# DRV8701E_jzk.net
KiCad netlist of a schematic drawn in EasyEDA Pro
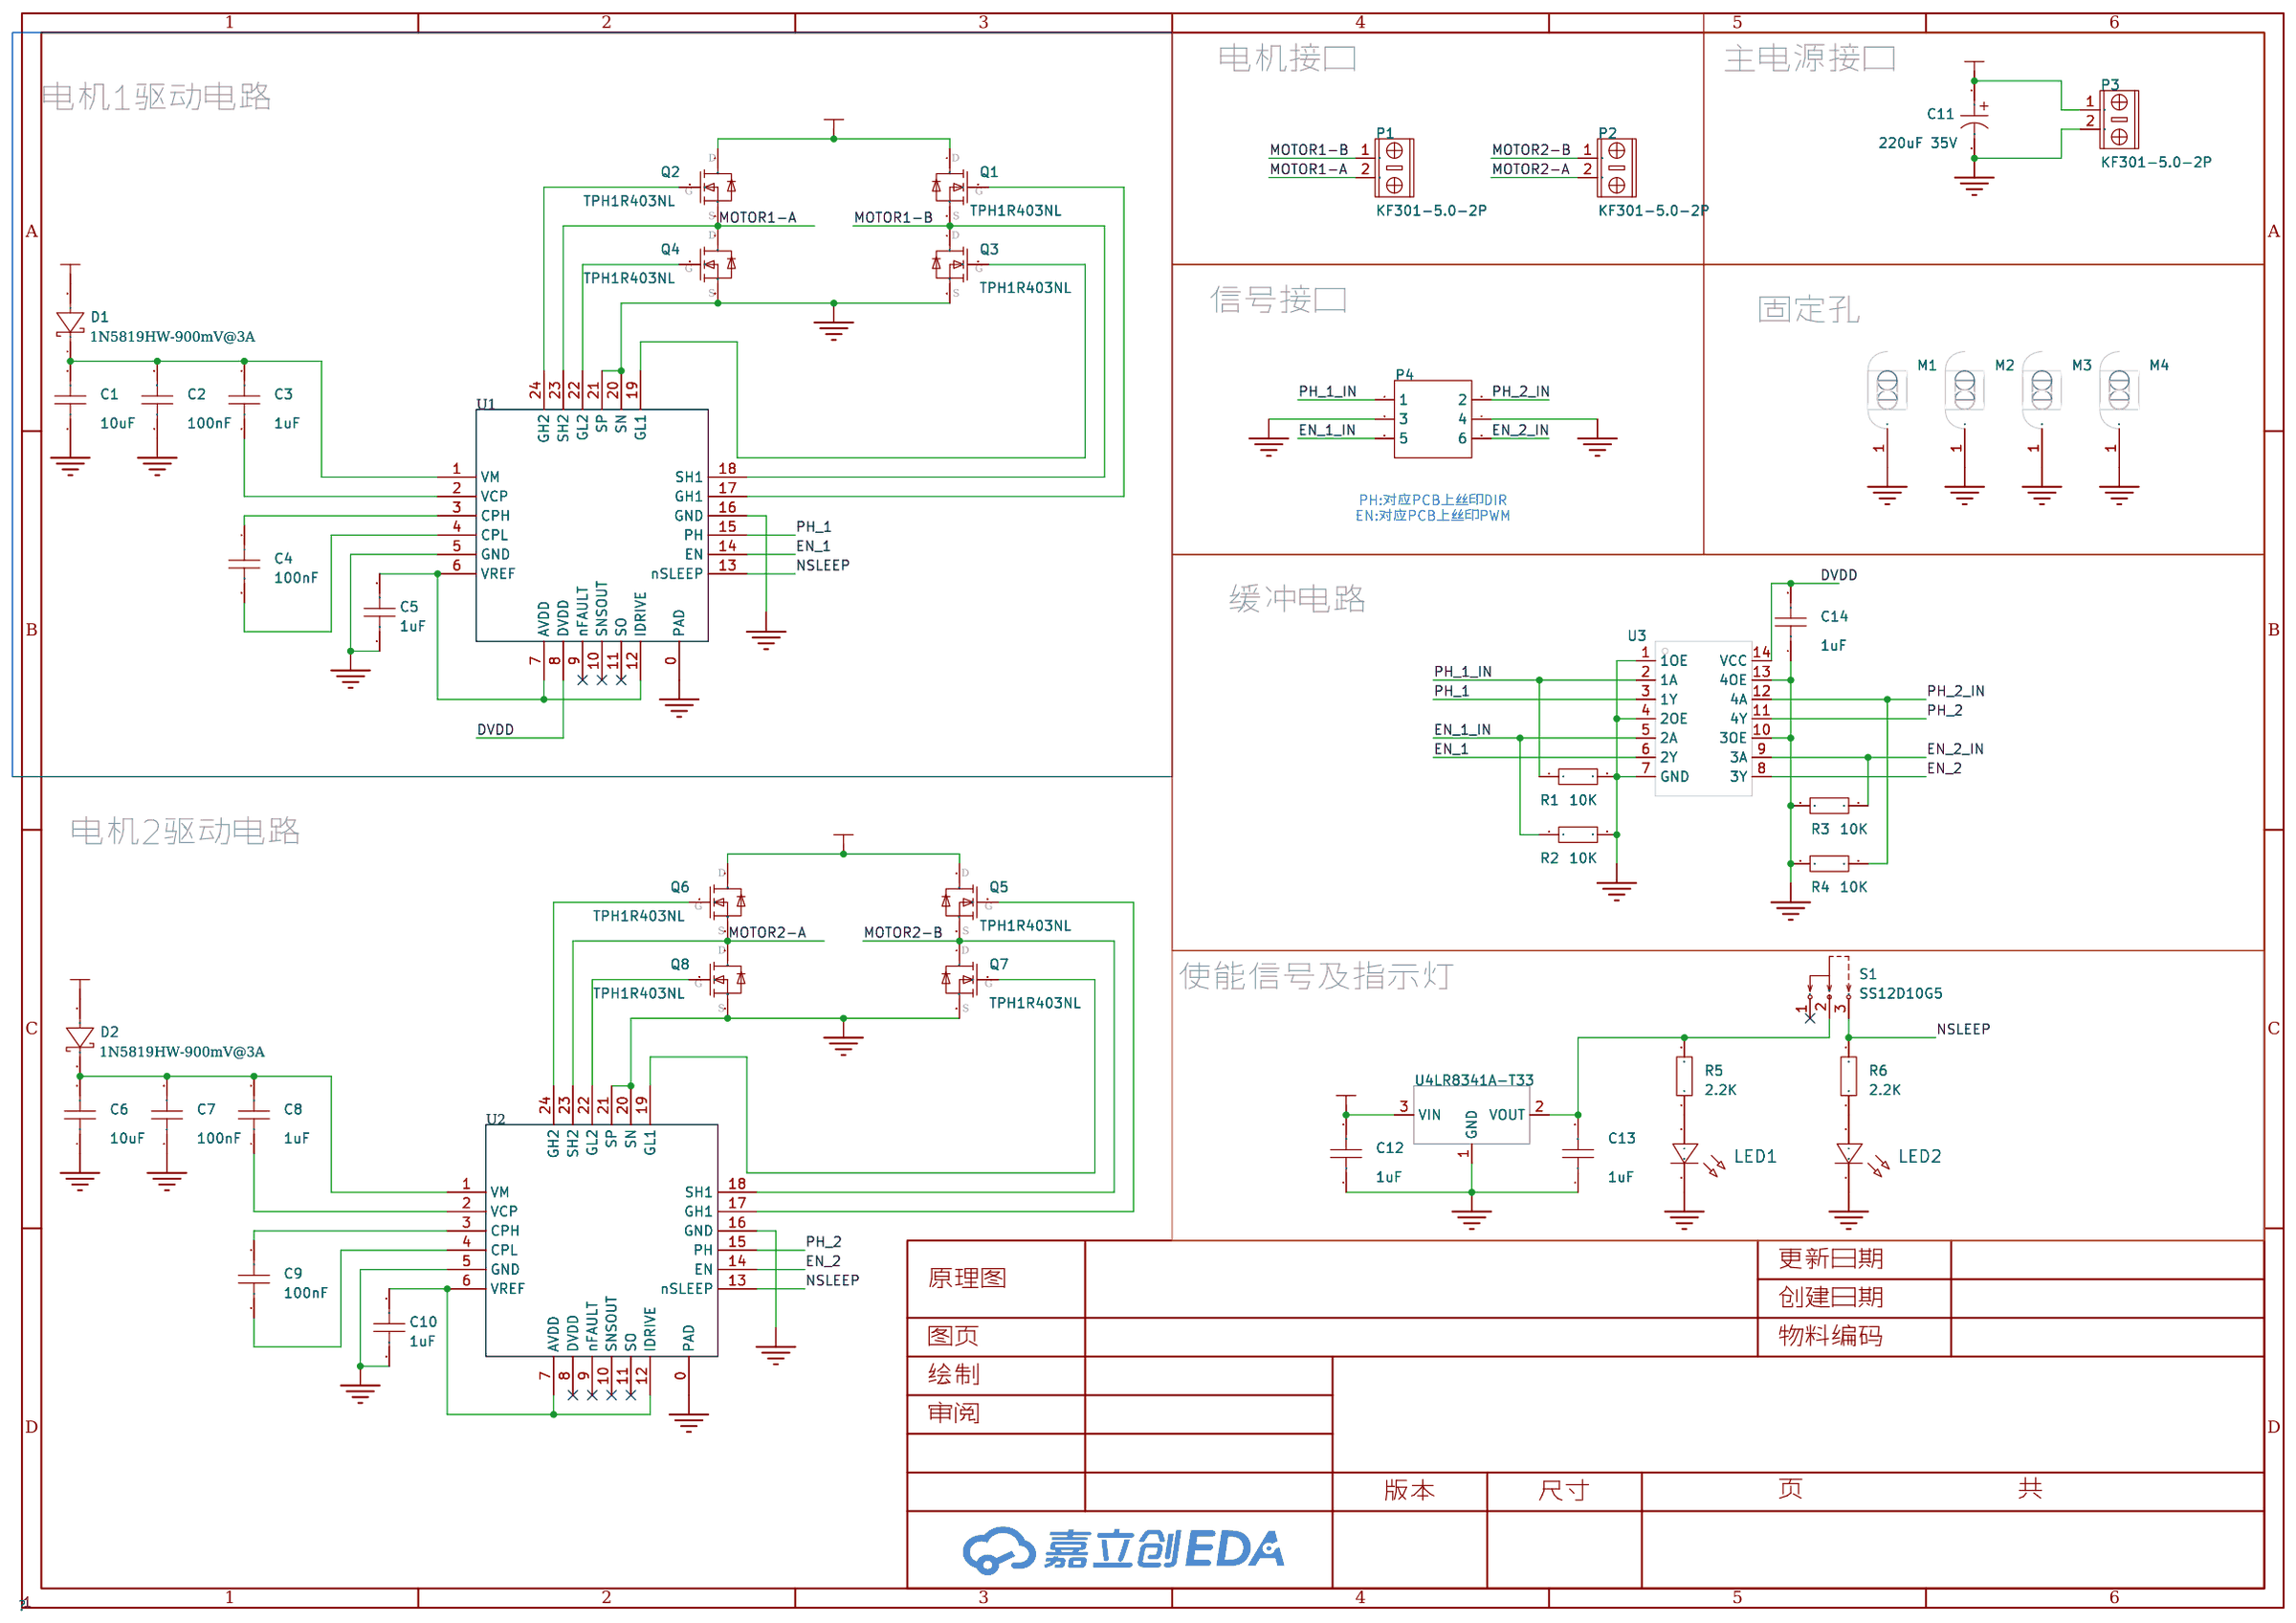
[diagram p0: schematic sheet]

(export (version "E")
  (design (tool "Eeschema 10.0.6"))
  (components
    (comp (ref "C1")
      (value "10uF")
      (footprint "easyedapro:C0805")
      (libsource (lib "easyedapro") (part "CapAcitance"))
    )
    (comp (ref "C2")
      (value "100nF")
      (footprint "easyedapro:C0805")
      (libsource (lib "easyedapro") (part "CapAcitance"))
    )
    (comp (ref "C3")
      (value "1uF")
      (footprint "easyedapro:C0805")
      (libsource (lib "easyedapro") (part "CapAcitance"))
    )
    (comp (ref "C4")
      (value "100nF")
      (footprint "easyedapro:C0805")
      (libsource (lib "easyedapro") (part "CapAcitance"))
    )
    (comp (ref "C5")
      (value "1uF")
      (footprint "easyedapro:C0805")
      (libsource (lib "easyedapro") (part "CapAcitance"))
    )
    (comp (ref "C6")
      (value "10uF")
      (footprint "easyedapro:C0805")
      (libsource (lib "easyedapro") (part "CapAcitance"))
    )
    (comp (ref "C7")
      (value "100nF")
      (footprint "easyedapro:C0805")
      (libsource (lib "easyedapro") (part "CapAcitance"))
    )
    (comp (ref "C8")
      (value "1uF")
      (footprint "easyedapro:C0805")
      (libsource (lib "easyedapro") (part "CapAcitance"))
    )
    (comp (ref "C9")
      (value "100nF")
      (footprint "easyedapro:C0805")
      (libsource (lib "easyedapro") (part "CapAcitance"))
    )
    (comp (ref "C10")
      (value "1uF")
      (footprint "easyedapro:C0805")
      (libsource (lib "easyedapro") (part "CapAcitance"))
    )
    (comp (ref "C11")
      (value "220uF 35V")
      (footprint "easyedapro:CAP-TH_BD8.0-P3.50-D0.6-FD-2")
      (description "容值:220uF;精度:±20%;额定电压:35V;纹波电流:1.7A@100kHz;等效串联电阻:40mΩ@100kHz;")
      (fields
        (field (name "Manufacturer Part") "KNH2220UF35V149EC0049")
        (field (name "Manufacturer") "KNSCHA(科尼盛)")
      )
      (libsource (lib "easyedapro") (part "KNH2220UF35V149EC0049"))
    )
    (comp (ref "C12")
      (value "1uF")
      (footprint "easyedapro:C0805")
      (libsource (lib "easyedapro") (part "CapAcitance"))
    )
    (comp (ref "C13")
      (value "1uF")
      (footprint "easyedapro:C0805")
      (libsource (lib "easyedapro") (part "CapAcitance"))
    )
    (comp (ref "C14")
      (value "1uF")
      (footprint "easyedapro:C0805")
      (libsource (lib "easyedapro") (part "CapAcitance"))
    )
    (comp (ref "D1")
      (value "1N5819HW-900mV@3A")
      (footprint "easyedapro:SOD-123_L2.7-W1.6-LS3.7-RD-1")
      (description "二极管配置:-;正向压降(Vf):900mV@3A;直流反向耐压(Vr):40V;平均整流电流(Io):1A;")
      (fields (field (name "Manufacturer") "TECH PUBLIC(台舟)"))
      (libsource (lib "easyedapro") (part "1N5819W_C2905650"))
    )
    (comp (ref "D2")
      (value "1N5819HW-900mV@3A")
      (footprint "easyedapro:SOD-123_L2.7-W1.6-LS3.7-RD-1")
      (description "二极管配置:-;正向压降(Vf):900mV@3A;直流反向耐压(Vr):40V;平均整流电流(Io):1A;")
      (fields (field (name "Manufacturer") "TECH PUBLIC(台舟)"))
      (libsource (lib "easyedapro") (part "1N5819W_C2905650"))
    )
    (comp (ref "LED1")
      (value "~")
      (footprint "easyedapro:LED_0603")
      (libsource (lib "easyedapro") (part "LED_R"))
    )
    (comp (ref "LED2")
      (value "~")
      (footprint "easyedapro:LED_0603")
      (libsource (lib "easyedapro") (part "LED_R"))
    )
    (comp (ref "M1")
      (value "~")
      (footprint "easyedapro:长圆形固定孔L5.0-O3.0")
      (libsource (lib "easyedapro") (part "长圆形固定孔L5.0-O3.0"))
    )
    (comp (ref "M2")
      (value "~")
      (footprint "easyedapro:长圆形固定孔L5.0-O3.0")
      (libsource (lib "easyedapro") (part "长圆形固定孔L5.0-O3.0"))
    )
    (comp (ref "M3")
      (value "~")
      (footprint "easyedapro:长圆形固定孔L5.0-O3.0")
      (libsource (lib "easyedapro") (part "长圆形固定孔L5.0-O3.0"))
    )
    (comp (ref "M4")
      (value "~")
      (footprint "easyedapro:长圆形固定孔L5.0-O3.0")
      (libsource (lib "easyedapro") (part "长圆形固定孔L5.0-O3.0"))
    )
    (comp (ref "P1")
      (value "KF301-5.0-2P")
      (footprint "easyedapro:CONN-TH_P5.00_KF301-5.0-2P")
      (fields (field (name "Manufacturer") "KEFA(科发)"))
      (libsource (lib "easyedapro") (part "KF301-5.0-2P"))
    )
    (comp (ref "P2")
      (value "KF301-5.0-2P")
      (footprint "easyedapro:CONN-TH_P5.00_KF301-5.0-2P")
      (fields (field (name "Manufacturer") "KEFA(科发)"))
      (libsource (lib "easyedapro") (part "KF301-5.0-2P"))
    )
    (comp (ref "P3")
      (value "KF301-5.0-2P")
      (footprint "easyedapro:CONN-TH_P5.00_KF301-5.0-2P")
      (fields (field (name "Manufacturer") "KEFA(科发)"))
      (libsource (lib "easyedapro") (part "KF301-5.0-2P"))
    )
    (comp (ref "P4")
      (value "~")
      (footprint "easyedapro:HDR-TH_6P-P2.54-V-F-R2-C3-S2.54")
      (libsource (lib "easyedapro") (part "HDR-F-2.54_2x3"))
    )
    (comp (ref "Q1")
      (value "TPH1R403NL")
      (footprint "easyedapro:DFN5x6")
      (libsource (lib "easyedapro") (part "TPH1R403NL"))
    )
    (comp (ref "Q2")
      (value "TPH1R403NL")
      (footprint "easyedapro:DFN5x6")
      (libsource (lib "easyedapro") (part "TPH1R403NL"))
    )
    (comp (ref "Q3")
      (value "TPH1R403NL")
      (footprint "easyedapro:DFN5x6")
      (libsource (lib "easyedapro") (part "TPH1R403NL"))
    )
    (comp (ref "Q4")
      (value "TPH1R403NL")
      (footprint "easyedapro:DFN5x6")
      (libsource (lib "easyedapro") (part "TPH1R403NL"))
    )
    (comp (ref "Q5")
      (value "TPH1R403NL")
      (footprint "easyedapro:DFN5x6")
      (libsource (lib "easyedapro") (part "TPH1R403NL"))
    )
    (comp (ref "Q6")
      (value "TPH1R403NL")
      (footprint "easyedapro:DFN5x6")
      (libsource (lib "easyedapro") (part "TPH1R403NL"))
    )
    (comp (ref "Q7")
      (value "TPH1R403NL")
      (footprint "easyedapro:DFN5x6")
      (libsource (lib "easyedapro") (part "TPH1R403NL"))
    )
    (comp (ref "Q8")
      (value "TPH1R403NL")
      (footprint "easyedapro:DFN5x6")
      (libsource (lib "easyedapro") (part "TPH1R403NL"))
    )
    (comp (ref "R1") (value "10K") (footprint "easyedapro:R0603") (libsource (lib "easyedapro") (part "电阻")))
    (comp (ref "R2") (value "10K") (footprint "easyedapro:R0603") (libsource (lib "easyedapro") (part "电阻")))
    (comp (ref "R3") (value "10K") (footprint "easyedapro:R0603") (libsource (lib "easyedapro") (part "电阻")))
    (comp (ref "R4") (value "10K") (footprint "easyedapro:R0603") (libsource (lib "easyedapro") (part "电阻")))
    (comp (ref "R5") (value "2.2K") (footprint "easyedapro:R0603") (libsource (lib "easyedapro") (part "电阻")))
    (comp (ref "R6") (value "2.2K") (footprint "easyedapro:R0603") (libsource (lib "easyedapro") (part "电阻")))
    (comp (ref "S1")
      (value "SS12D10G5")
      (footprint "easyedapro:SW-TH_SHOU-HAN_SS12D10G4")
      (description "电路结构:单刀双掷;安装方式:直插;额定电流(DC):2A;额定电压(DC):125V;机械寿命:3千次;")
      (fields (field (name "Manufacturer") "SHOU HAN(首韩)"))
      (libsource (lib "easyedapro") (part "SS12D10G5"))
    )
    (comp (ref "U1")
      (value "~")
      (footprint "easyedapro:VQFN-24_L4.0-W4.0-P0.50-TL-EP2.8")
      (fields (field (name "Manufacturer") "Texas Instruments"))
      (libsource (lib "easyedapro") (part "DRV8701ERGER"))
    )
    (comp (ref "U2")
      (value "~")
      (footprint "easyedapro:VQFN-24_L4.0-W4.0-P0.50-TL-EP2.8")
      (fields (field (name "Manufacturer") "Texas Instruments"))
      (libsource (lib "easyedapro") (part "DRV8701ERGER"))
    )
    (comp (ref "U3")
      (value "SN74HC125PWR")
      (footprint "easyedapro:TSSOP-14_L5.0-W4.4-P0.65-LS6.5-BL")
      (fields (field (name "Manufacturer") "TI(德州仪器)"))
      (libsource (lib "easyedapro") (part "SN74HC125PWR"))
    )
    (comp (ref "U4")
      (value "LR8341A-T33")
      (footprint "easyedapro:SOT-23-3L_L2.9-W1.6-P1.90-LS2.8-BL")
      (description "输出类型:固定;最大输入电压:40V;输出电压:3.3V;最大输出电流:100mA;电源纹波抑制比(PSRR):55dB@(1kHz);输出极性:正极;")
      (fields (field (name "Manufacturer") "LR(朗瑞)"))
      (libsource (lib "easyedapro") (part "LR8341A-T33"))
    )
  )
  (nets
    (net (code "1") (name "/DVDD") (class "Default")
      (node (ref "C14") (pin "2") (pinfunction "2_2") (pintype "input"))
      (node (ref "U1") (pin "8") (pinfunction "DVDD_8") (pintype "input"))
      (node (ref "U3") (pin "14") (pinfunction "VCC_14") (pintype "input"))
    )
    (net (code "2") (name "/EN_1") (class "Default")
      (node (ref "U1") (pin "14") (pinfunction "EN_14") (pintype "input"))
      (node (ref "U3") (pin "6") (pinfunction "2Y_6") (pintype "input"))
    )
    (net (code "3") (name "/EN_1_IN") (class "Default")
      (node (ref "P4") (pin "5") (pinfunction "5_5") (pintype "input"))
      (node (ref "R2") (pin "1") (pinfunction "1_1") (pintype "input"))
      (node (ref "U3") (pin "5") (pinfunction "2A_5") (pintype "input"))
    )
    (net (code "4") (name "/EN_2") (class "Default")
      (node (ref "U2") (pin "14") (pinfunction "EN_14") (pintype "input"))
      (node (ref "U3") (pin "8") (pinfunction "3Y_8") (pintype "input"))
    )
    (net (code "5") (name "/EN_2_IN") (class "Default")
      (node (ref "P4") (pin "6") (pinfunction "6_6") (pintype "input"))
      (node (ref "R3") (pin "1") (pinfunction "1_1") (pintype "input"))
      (node (ref "U3") (pin "9") (pinfunction "3A_9") (pintype "input"))
    )
    (net (code "6") (name "/MOTOR1-A") (class "Default")
      (node (ref "P1") (pin "2") (pinfunction "2_2") (pintype "unspecified"))
      (node (ref "Q2") (pin "3") (pinfunction "S_3") (pintype "input"))
      (node (ref "Q4") (pin "1") (pinfunction "D_1") (pintype "input"))
      (node (ref "U1") (pin "23") (pinfunction "SH2_23") (pintype "input"))
    )
    (net (code "7") (name "/MOTOR1-B") (class "Default")
      (node (ref "P1") (pin "1") (pinfunction "1_1") (pintype "unspecified"))
      (node (ref "Q1") (pin "3") (pinfunction "S_3") (pintype "input"))
      (node (ref "Q3") (pin "1") (pinfunction "D_1") (pintype "input"))
      (node (ref "U1") (pin "18") (pinfunction "SH1_18") (pintype "input"))
    )
    (net (code "8") (name "/MOTOR2-A") (class "Default")
      (node (ref "P2") (pin "2") (pinfunction "2_2") (pintype "unspecified"))
      (node (ref "Q6") (pin "3") (pinfunction "S_3") (pintype "input"))
      (node (ref "Q8") (pin "1") (pinfunction "D_1") (pintype "input"))
      (node (ref "U2") (pin "23") (pinfunction "SH2_23") (pintype "input"))
    )
    (net (code "9") (name "/MOTOR2-B") (class "Default")
      (node (ref "P2") (pin "1") (pinfunction "1_1") (pintype "unspecified"))
      (node (ref "Q5") (pin "3") (pinfunction "S_3") (pintype "input"))
      (node (ref "Q7") (pin "1") (pinfunction "D_1") (pintype "input"))
      (node (ref "U2") (pin "18") (pinfunction "SH1_18") (pintype "input"))
    )
    (net (code "10") (name "/NSLEEP") (class "Default")
      (node (ref "R6") (pin "1") (pinfunction "1_1") (pintype "input"))
      (node (ref "S1") (pin "3") (pinfunction "3_3") (pintype "unspecified"))
      (node (ref "U1") (pin "13") (pinfunction "nSLEEP_13") (pintype "input"))
      (node (ref "U2") (pin "13") (pinfunction "nSLEEP_13") (pintype "input"))
    )
    (net (code "11") (name "/PH_1") (class "Default")
      (node (ref "U1") (pin "15") (pinfunction "PH_15") (pintype "input"))
      (node (ref "U3") (pin "3") (pinfunction "1Y_3") (pintype "input"))
    )
    (net (code "12") (name "/PH_1_IN") (class "Default")
      (node (ref "P4") (pin "1") (pinfunction "1_1") (pintype "input"))
      (node (ref "R1") (pin "1") (pinfunction "1_1") (pintype "input"))
      (node (ref "U3") (pin "2") (pinfunction "1A_2") (pintype "input"))
    )
    (net (code "13") (name "/PH_2") (class "Default")
      (node (ref "U2") (pin "15") (pinfunction "PH_15") (pintype "input"))
      (node (ref "U3") (pin "11") (pinfunction "4Y_11") (pintype "input"))
    )
    (net (code "14") (name "/PH_2_IN") (class "Default")
      (node (ref "P4") (pin "2") (pinfunction "2_2") (pintype "input"))
      (node (ref "R4") (pin "1") (pinfunction "1_1") (pintype "input"))
      (node (ref "U3") (pin "12") (pinfunction "4A_12") (pintype "input"))
    )
    (net (code "15") (name "GND") (class "Default")
      (node (ref "C1") (pin "1") (pinfunction "1_1") (pintype "input"))
      (node (ref "C10") (pin "1") (pinfunction "1_1") (pintype "input"))
      (node (ref "C11") (pin "2") (pinfunction "2_2") (pintype "input"))
      (node (ref "C12") (pin "1") (pinfunction "1_1") (pintype "input"))
      (node (ref "C13") (pin "1") (pinfunction "1_1") (pintype "input"))
      (node (ref "C14") (pin "1") (pinfunction "1_1") (pintype "input"))
      (node (ref "C2") (pin "1") (pinfunction "1_1") (pintype "input"))
      (node (ref "C5") (pin "1") (pinfunction "1_1") (pintype "input"))
      (node (ref "C6") (pin "1") (pinfunction "1_1") (pintype "input"))
      (node (ref "C7") (pin "1") (pinfunction "1_1") (pintype "input"))
      (node (ref "LED1") (pin "1") (pinfunction "C_1") (pintype "input"))
      (node (ref "LED2") (pin "1") (pinfunction "C_1") (pintype "input"))
      (node (ref "M1") (pin "1") (pinfunction "1_1") (pintype "input"))
      (node (ref "M2") (pin "1") (pinfunction "1_1") (pintype "input"))
      (node (ref "M3") (pin "1") (pinfunction "1_1") (pintype "input"))
      (node (ref "M4") (pin "1") (pinfunction "1_1") (pintype "input"))
      (node (ref "P3") (pin "2") (pinfunction "2_2") (pintype "unspecified"))
      (node (ref "P4") (pin "3") (pinfunction "3_3") (pintype "input"))
      (node (ref "P4") (pin "4") (pinfunction "4_4") (pintype "input"))
      (node (ref "Q3") (pin "3") (pinfunction "S_3") (pintype "input"))
      (node (ref "Q4") (pin "3") (pinfunction "S_3") (pintype "input"))
      (node (ref "Q7") (pin "3") (pinfunction "S_3") (pintype "input"))
      (node (ref "Q8") (pin "3") (pinfunction "S_3") (pintype "input"))
      (node (ref "R1") (pin "2") (pinfunction "2_2") (pintype "input"))
      (node (ref "R2") (pin "2") (pinfunction "2_2") (pintype "input"))
      (node (ref "R3") (pin "2") (pinfunction "2_2") (pintype "input"))
      (node (ref "R4") (pin "2") (pinfunction "2_2") (pintype "input"))
      (node (ref "U1") (pin "0") (pinfunction "PAD_0") (pintype "input"))
      (node (ref "U1") (pin "16") (pinfunction "GND_16") (pintype "input"))
      (node (ref "U1") (pin "20") (pinfunction "SN_20") (pintype "input"))
      (node (ref "U1") (pin "21") (pinfunction "SP_21") (pintype "input"))
      (node (ref "U1") (pin "5") (pinfunction "GND_5") (pintype "input"))
      (node (ref "U2") (pin "0") (pinfunction "PAD_0") (pintype "input"))
      (node (ref "U2") (pin "16") (pinfunction "GND_16") (pintype "input"))
      (node (ref "U2") (pin "20") (pinfunction "SN_20") (pintype "input"))
      (node (ref "U2") (pin "21") (pinfunction "SP_21") (pintype "input"))
      (node (ref "U2") (pin "5") (pinfunction "GND_5") (pintype "input"))
      (node (ref "U3") (pin "1") (pinfunction "1OE_1") (pintype "input"))
      (node (ref "U3") (pin "10") (pinfunction "3OE_10") (pintype "input"))
      (node (ref "U3") (pin "13") (pinfunction "4OE_13") (pintype "input"))
      (node (ref "U3") (pin "4") (pinfunction "2OE_4") (pintype "input"))
      (node (ref "U3") (pin "7") (pinfunction "GND_7") (pintype "input"))
      (node (ref "U4") (pin "1") (pinfunction "GND_1") (pintype "unspecified"))
    )
    (net (code "16") (name "Net-(D1-K)") (class "Default")
      (node (ref "C1") (pin "2") (pinfunction "2_2") (pintype "input"))
      (node (ref "C2") (pin "2") (pinfunction "2_2") (pintype "input"))
      (node (ref "C3") (pin "2") (pinfunction "2_2") (pintype "input"))
      (node (ref "D1") (pin "1") (pinfunction "K_1") (pintype "input"))
      (node (ref "U1") (pin "1") (pinfunction "VM_1") (pintype "input"))
    )
    (net (code "17") (name "Net-(D2-K)") (class "Default")
      (node (ref "C6") (pin "2") (pinfunction "2_2") (pintype "input"))
      (node (ref "C7") (pin "2") (pinfunction "2_2") (pintype "input"))
      (node (ref "C8") (pin "2") (pinfunction "2_2") (pintype "input"))
      (node (ref "D2") (pin "1") (pinfunction "K_1") (pintype "input"))
      (node (ref "U2") (pin "1") (pinfunction "VM_1") (pintype "input"))
    )
    (net (code "18") (name "Net-(LED1-A)") (class "Default")
      (node (ref "LED1") (pin "2") (pinfunction "A_2") (pintype "input"))
      (node (ref "R5") (pin "1") (pinfunction "1_1") (pintype "input"))
    )
    (net (code "19") (name "Net-(LED2-A)") (class "Default")
      (node (ref "LED2") (pin "2") (pinfunction "A_2") (pintype "input"))
      (node (ref "R6") (pin "2") (pinfunction "2_2") (pintype "input"))
    )
    (net (code "20") (name "Net-(Q1-G)") (class "Default")
      (node (ref "Q1") (pin "2") (pinfunction "G_2") (pintype "input"))
      (node (ref "U1") (pin "17") (pinfunction "GH1_17") (pintype "input"))
    )
    (net (code "21") (name "Net-(Q2-G)") (class "Default")
      (node (ref "Q2") (pin "2") (pinfunction "G_2") (pintype "input"))
      (node (ref "U1") (pin "24") (pinfunction "GH2_24") (pintype "input"))
    )
    (net (code "22") (name "Net-(Q3-G)") (class "Default")
      (node (ref "Q3") (pin "2") (pinfunction "G_2") (pintype "input"))
      (node (ref "U1") (pin "19") (pinfunction "GL1_19") (pintype "output"))
    )
    (net (code "23") (name "Net-(Q4-G)") (class "Default")
      (node (ref "Q4") (pin "2") (pinfunction "G_2") (pintype "input"))
      (node (ref "U1") (pin "22") (pinfunction "GL2_22") (pintype "output"))
    )
    (net (code "24") (name "Net-(Q5-G)") (class "Default")
      (node (ref "Q5") (pin "2") (pinfunction "G_2") (pintype "input"))
      (node (ref "U2") (pin "17") (pinfunction "GH1_17") (pintype "input"))
    )
    (net (code "25") (name "Net-(Q6-G)") (class "Default")
      (node (ref "Q6") (pin "2") (pinfunction "G_2") (pintype "input"))
      (node (ref "U2") (pin "24") (pinfunction "GH2_24") (pintype "input"))
    )
    (net (code "26") (name "Net-(Q7-G)") (class "Default")
      (node (ref "Q7") (pin "2") (pinfunction "G_2") (pintype "input"))
      (node (ref "U2") (pin "19") (pinfunction "GL1_19") (pintype "output"))
    )
    (net (code "27") (name "Net-(Q8-G)") (class "Default")
      (node (ref "Q8") (pin "2") (pinfunction "G_2") (pintype "input"))
      (node (ref "U2") (pin "22") (pinfunction "GL2_22") (pintype "output"))
    )
    (net (code "28") (name "Net-(U1-AVDD)") (class "Default")
      (node (ref "C5") (pin "2") (pinfunction "2_2") (pintype "input"))
      (node (ref "U1") (pin "12") (pinfunction "IDRIVE_12") (pintype "input"))
      (node (ref "U1") (pin "6") (pinfunction "VREF_6") (pintype "input"))
      (node (ref "U1") (pin "7") (pinfunction "AVDD_7") (pintype "input"))
    )
    (net (code "29") (name "Net-(U1-CPH)") (class "Default")
      (node (ref "C4") (pin "1") (pinfunction "1_1") (pintype "input"))
      (node (ref "U1") (pin "3") (pinfunction "CPH_3") (pintype "input"))
    )
    (net (code "30") (name "Net-(U1-CPL)") (class "Default")
      (node (ref "C4") (pin "2") (pinfunction "2_2") (pintype "input"))
      (node (ref "U1") (pin "4") (pinfunction "CPL_4") (pintype "input"))
    )
    (net (code "31") (name "Net-(U1-VCP)") (class "Default")
      (node (ref "C3") (pin "1") (pinfunction "1_1") (pintype "input"))
      (node (ref "U1") (pin "2") (pinfunction "VCP_2") (pintype "input"))
    )
    (net (code "32") (name "Net-(U2-AVDD)") (class "Default")
      (node (ref "C10") (pin "2") (pinfunction "2_2") (pintype "input"))
      (node (ref "U2") (pin "12") (pinfunction "IDRIVE_12") (pintype "input"))
      (node (ref "U2") (pin "6") (pinfunction "VREF_6") (pintype "input"))
      (node (ref "U2") (pin "7") (pinfunction "AVDD_7") (pintype "input"))
    )
    (net (code "33") (name "Net-(U2-CPH)") (class "Default")
      (node (ref "C9") (pin "1") (pinfunction "1_1") (pintype "input"))
      (node (ref "U2") (pin "3") (pinfunction "CPH_3") (pintype "input"))
    )
    (net (code "34") (name "Net-(U2-CPL)") (class "Default")
      (node (ref "C9") (pin "2") (pinfunction "2_2") (pintype "input"))
      (node (ref "U2") (pin "4") (pinfunction "CPL_4") (pintype "input"))
    )
    (net (code "35") (name "Net-(U2-VCP)") (class "Default")
      (node (ref "C8") (pin "1") (pinfunction "1_1") (pintype "input"))
      (node (ref "U2") (pin "2") (pinfunction "VCP_2") (pintype "input"))
    )
    (net (code "36") (name "Net-(U4-VOUT)") (class "Default")
      (node (ref "C13") (pin "2") (pinfunction "2_2") (pintype "input"))
      (node (ref "R5") (pin "2") (pinfunction "2_2") (pintype "input"))
      (node (ref "S1") (pin "2") (pinfunction "2_2") (pintype "unspecified"))
      (node (ref "U4") (pin "2") (pinfunction "VOUT_2") (pintype "unspecified"))
    )
    (net (code "37") (name "VIN") (class "Default")
      (node (ref "C11") (pin "1") (pinfunction "1_1") (pintype "input"))
      (node (ref "C12") (pin "2") (pinfunction "2_2") (pintype "input"))
      (node (ref "D1") (pin "2") (pinfunction "A_2") (pintype "input"))
      (node (ref "D2") (pin "2") (pinfunction "A_2") (pintype "input"))
      (node (ref "P3") (pin "1") (pinfunction "1_1") (pintype "unspecified"))
      (node (ref "Q1") (pin "1") (pinfunction "D_1") (pintype "input"))
      (node (ref "Q2") (pin "1") (pinfunction "D_1") (pintype "input"))
      (node (ref "Q5") (pin "1") (pinfunction "D_1") (pintype "input"))
      (node (ref "Q6") (pin "1") (pinfunction "D_1") (pintype "input"))
      (node (ref "U4") (pin "3") (pinfunction "VIN_3") (pintype "unspecified"))
    )
    (net (code "38") (name "unconnected-(S1-Pad1)") (class "Default")
      (node (ref "S1") (pin "1") (pinfunction "1_1") (pintype "unspecified+no_connect"))
    )
    (net (code "39") (name "unconnected-(U1-SNSOUT-Pad10)") (class "Default")
      (node (ref "U1") (pin "10") (pinfunction "SNSOUT_10") (pintype "input+no_connect"))
    )
    (net (code "40") (name "unconnected-(U1-SO-Pad11)") (class "Default")
      (node (ref "U1") (pin "11") (pinfunction "SO_11") (pintype "output+no_connect"))
    )
    (net (code "41") (name "unconnected-(U1-nFAULT-Pad9)") (class "Default")
      (node (ref "U1") (pin "9") (pinfunction "nFAULT_9") (pintype "input+no_connect"))
    )
    (net (code "42") (name "unconnected-(U2-DVDD-Pad8)") (class "Default")
      (node (ref "U2") (pin "8") (pinfunction "DVDD_8") (pintype "input+no_connect"))
    )
    (net (code "43") (name "unconnected-(U2-SNSOUT-Pad10)") (class "Default")
      (node (ref "U2") (pin "10") (pinfunction "SNSOUT_10") (pintype "input+no_connect"))
    )
    (net (code "44") (name "unconnected-(U2-SO-Pad11)") (class "Default")
      (node (ref "U2") (pin "11") (pinfunction "SO_11") (pintype "output+no_connect"))
    )
    (net (code "45") (name "unconnected-(U2-nFAULT-Pad9)") (class "Default")
      (node (ref "U2") (pin "9") (pinfunction "nFAULT_9") (pintype "input+no_connect"))
    )
  )
)
